# PowerModule_Testboard.net
KiCad netlist of a schematic drawn in EAGLE
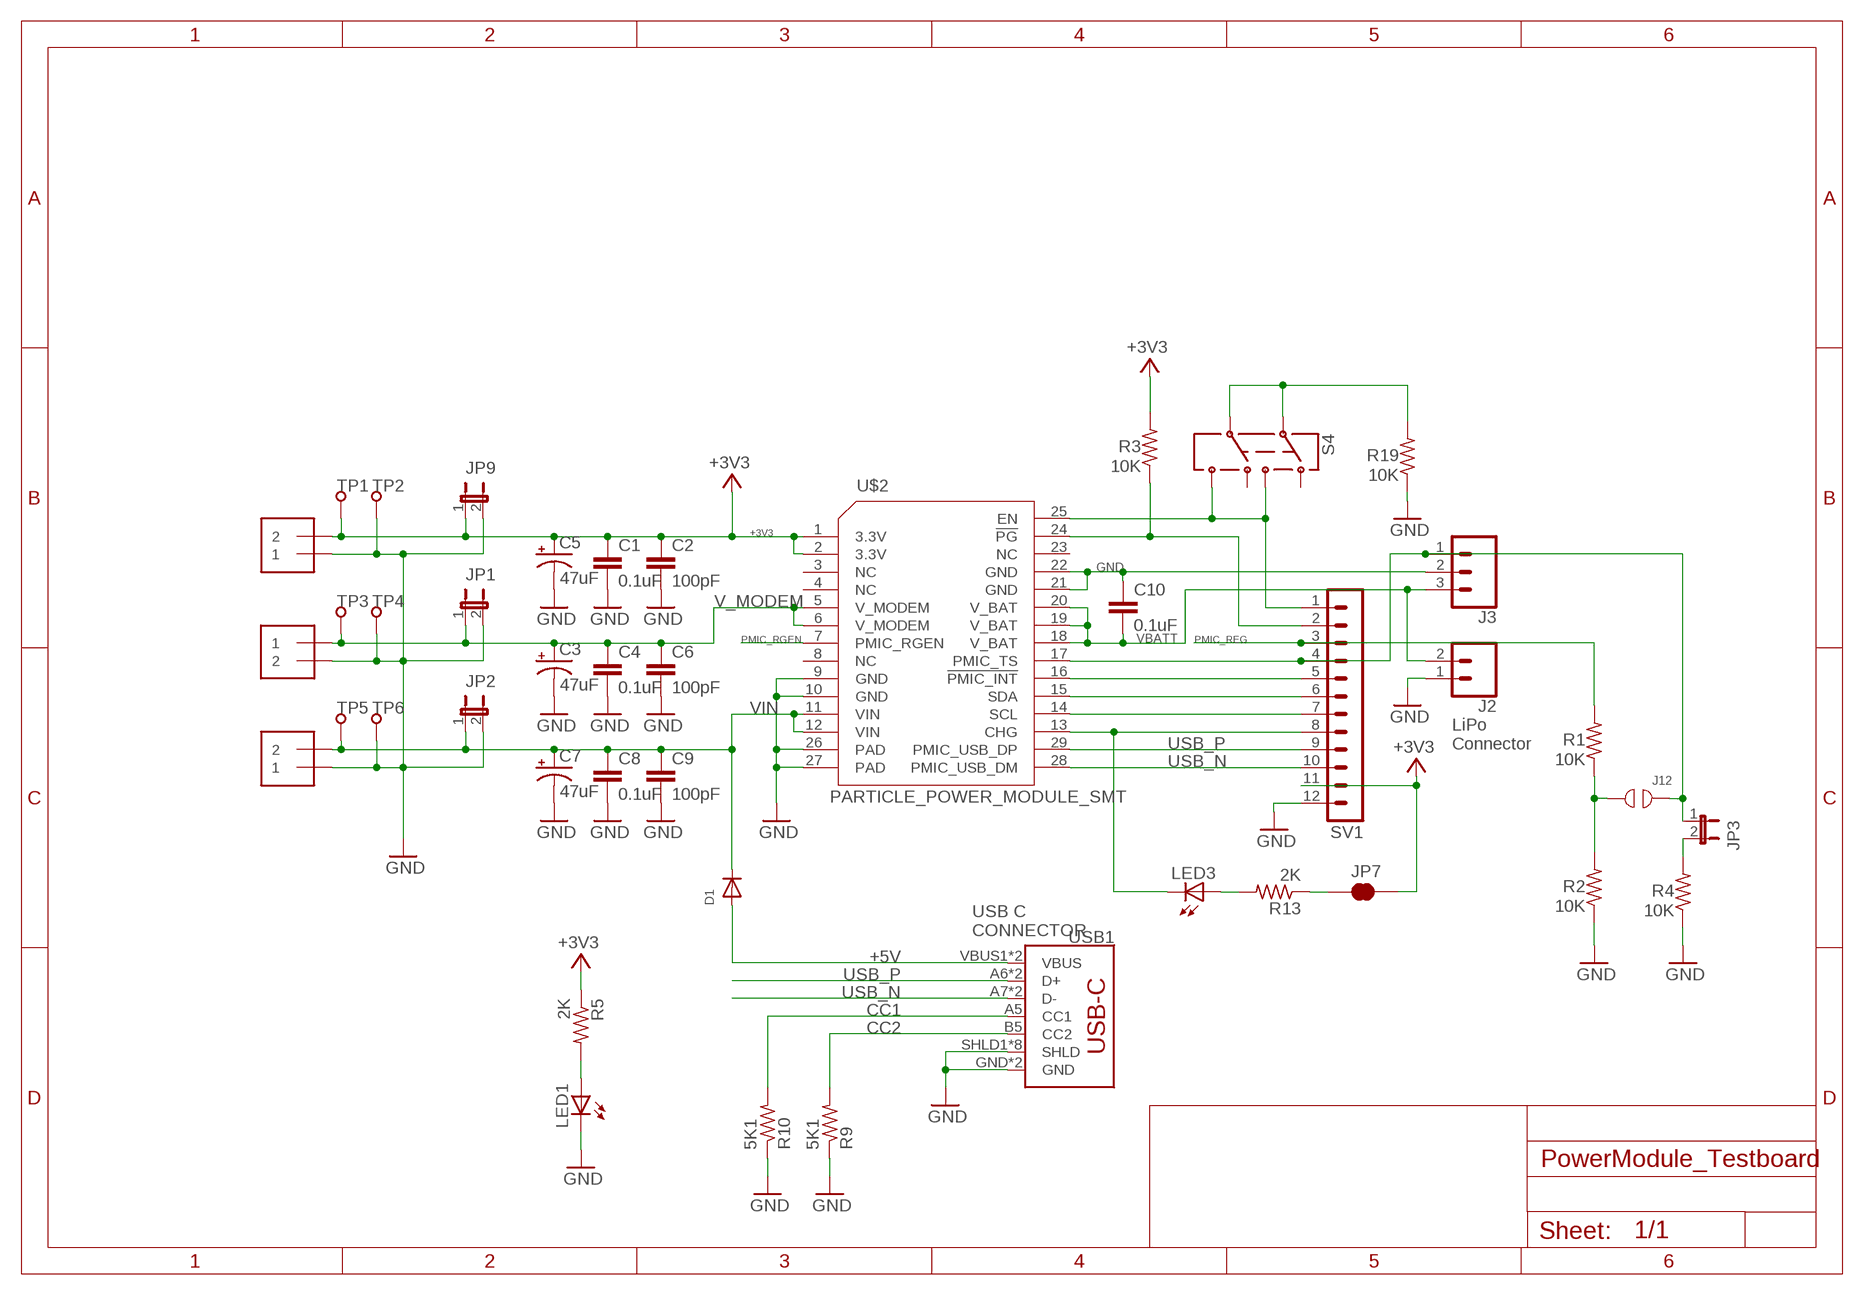
[diagram p0: schematic, sheet 1]

(export (version "E")
  (design (tool "Eeschema 10.0.6"))
  (components
    (comp (ref "C1")
      (value "0.1uF")
      (footprint "eagle-import:0603")
      (libsource (lib "eagle-import") (part "0.1UF-0603-25V-5%"))
    )
    (comp (ref "C2")
      (value "100pF")
      (footprint "eagle-import:0603")
      (libsource (lib "eagle-import") (part "0.1UF-0603-25V-5%"))
    )
    (comp (ref "C3")
      (value "47uF")
      (footprint "eagle-import:NIC_10X10.5_CAP")
      (libsource (lib "eagle-import") (part "100UF-POLAR-10X10.5-63V-20%"))
    )
    (comp (ref "C4")
      (value "0.1uF")
      (footprint "eagle-import:0603")
      (libsource (lib "eagle-import") (part "0.1UF-0603-25V-5%"))
    )
    (comp (ref "C5")
      (value "47uF")
      (footprint "eagle-import:NIC_10X10.5_CAP")
      (libsource (lib "eagle-import") (part "100UF-POLAR-10X10.5-63V-20%"))
    )
    (comp (ref "C6")
      (value "100pF")
      (footprint "eagle-import:0603")
      (libsource (lib "eagle-import") (part "0.1UF-0603-25V-5%"))
    )
    (comp (ref "C7")
      (value "47uF")
      (footprint "eagle-import:NIC_10X10.5_CAP")
      (libsource (lib "eagle-import") (part "100UF-POLAR-10X10.5-63V-20%"))
    )
    (comp (ref "C8")
      (value "0.1uF")
      (footprint "eagle-import:0603")
      (libsource (lib "eagle-import") (part "0.1UF-0603-25V-5%"))
    )
    (comp (ref "C9")
      (value "100pF")
      (footprint "eagle-import:0603")
      (libsource (lib "eagle-import") (part "0.1UF-0603-25V-5%"))
    )
    (comp (ref "C10")
      (value "0.1uF")
      (footprint "eagle-import:0603")
      (libsource (lib "eagle-import") (part "0.1UF-0603-25V-5%"))
    )
    (comp (ref "D1")
      (value "DIODE_SOD-123FL")
      (footprint "eagle-import:SOD-123FL")
      (libsource (lib "eagle-import") (part "DIODE_SOD-123FL"))
    )
    (comp (ref "J1")
      (value "1X2-3.5MM")
      (footprint "eagle-import:1X2-3.5MM")
      (libsource (lib "eagle-import") (part "1X2-3.5MM"))
    )
    (comp (ref "J2")
      (value "CONN_02-JST-2MM-SMT")
      (footprint "eagle-import:JST-2-SMD@2")
      (libsource (lib "eagle-import") (part "CONN_02-JST-2MM-SMT"))
    )
    (comp (ref "J3")
      (value "CONN_03JST-SMD-VERT")
      (footprint "eagle-import:JST-3-SMD-VERT")
      (libsource (lib "eagle-import") (part "CONN_03JST-SMD-VERT"))
    )
    (comp (ref "J4")
      (value "1X2-3.5MM")
      (footprint "eagle-import:1X2-3.5MM")
      (libsource (lib "eagle-import") (part "1X2-3.5MM"))
    )
    (comp (ref "J5")
      (value "1X2-3.5MM")
      (footprint "eagle-import:1X2-3.5MM")
      (libsource (lib "eagle-import") (part "1X2-3.5MM"))
    )
    (comp (ref "J12")
      (value "TP_OPEN")
      (footprint "eagle-import:TP_OPEN")
      (libsource (lib "eagle-import") (part "TP_OPEN"))
    )
    (comp (ref "JP1")
      (value "JUMPER2")
      (footprint "eagle-import:JUMPER2")
      (libsource (lib "eagle-import") (part "JUMPER2"))
    )
    (comp (ref "JP2")
      (value "JUMPER2")
      (footprint "eagle-import:JUMPER2")
      (libsource (lib "eagle-import") (part "JUMPER2"))
    )
    (comp (ref "JP3")
      (value "JUMPER2")
      (footprint "eagle-import:JUMPER2")
      (libsource (lib "eagle-import") (part "JUMPER2"))
    )
    (comp (ref "JP7")
      (value "JUMPER-SMT_2_NC_TRACE_NO-SILK")
      (footprint "eagle-import:SMT-JUMPER_2_NC_TRACE_NO-SILK")
      (libsource (lib "eagle-import") (part "JUMPER-SMT_2_NC_TRACE_NO-SILK"))
    )
    (comp (ref "JP9")
      (value "JUMPER2")
      (footprint "eagle-import:JUMPER2")
      (libsource (lib "eagle-import") (part "JUMPER2"))
    )
    (comp (ref "LED1")
      (value "LEDCHIP-LED0603")
      (footprint "eagle-import:CHIP-LED0603")
      (libsource (lib "eagle-import") (part "LEDCHIP-LED0603"))
    )
    (comp (ref "LED3")
      (value "LEDCHIP-LED0603")
      (footprint "eagle-import:CHIP-LED0603")
      (libsource (lib "eagle-import") (part "LEDCHIP-LED0603"))
    )
    (comp (ref "R1")
      (value "10K")
      (footprint "eagle-import:R0603_P")
      (libsource (lib "eagle-import") (part "RES_0603100K_"))
    )
    (comp (ref "R2")
      (value "10K")
      (footprint "eagle-import:R0603_P")
      (libsource (lib "eagle-import") (part "RES_0603100K_"))
    )
    (comp (ref "R3")
      (value "10K")
      (footprint "eagle-import:R0603_P")
      (libsource (lib "eagle-import") (part "RES_0603100K_"))
    )
    (comp (ref "R4")
      (value "10K")
      (footprint "eagle-import:R0603_P")
      (libsource (lib "eagle-import") (part "RES_0603100K_"))
    )
    (comp (ref "R5")
      (value "2K")
      (footprint "eagle-import:R0603_P")
      (libsource (lib "eagle-import") (part "RES_06032K2_"))
    )
    (comp (ref "R9")
      (value "5K1")
      (footprint "eagle-import:R0603_P")
      (libsource (lib "eagle-import") (part "RES_0603"))
    )
    (comp (ref "R10")
      (value "5K1")
      (footprint "eagle-import:R0603_P")
      (libsource (lib "eagle-import") (part "RES_0603"))
    )
    (comp (ref "R13")
      (value "2K")
      (footprint "eagle-import:R0603_P")
      (libsource (lib "eagle-import") (part "RES_06032K2_"))
    )
    (comp (ref "R19")
      (value "10K")
      (footprint "eagle-import:R0603_P")
      (libsource (lib "eagle-import") (part "RES_0603100K_"))
    )
    (comp (ref "S4")
      (value "SWITCH-DPDT")
      (footprint "eagle-import:SWITCH-2.5X3.2-6")
      (libsource (lib "eagle-import") (part "SWITCH-DPDT"))
    )
    (comp (ref "SV1")
      (value "MA12-1")
      (footprint "eagle-import:MA12-1")
      (libsource (lib "eagle-import") (part "MA12-1"))
    )
    (comp (ref "TP1")
      (value "TP-S2751-46R")
      (footprint "eagle-import:S2751-46R")
      (libsource (lib "eagle-import") (part "TP-S2751-46R"))
    )
    (comp (ref "TP2")
      (value "TP-S2751-46R")
      (footprint "eagle-import:S2751-46R")
      (libsource (lib "eagle-import") (part "TP-S2751-46R"))
    )
    (comp (ref "TP3")
      (value "TP-S2751-46R")
      (footprint "eagle-import:S2751-46R")
      (libsource (lib "eagle-import") (part "TP-S2751-46R"))
    )
    (comp (ref "TP4")
      (value "TP-S2751-46R")
      (footprint "eagle-import:S2751-46R")
      (libsource (lib "eagle-import") (part "TP-S2751-46R"))
    )
    (comp (ref "TP5")
      (value "TP-S2751-46R")
      (footprint "eagle-import:S2751-46R")
      (libsource (lib "eagle-import") (part "TP-S2751-46R"))
    )
    (comp (ref "TP6")
      (value "TP-S2751-46R")
      (footprint "eagle-import:S2751-46R")
      (libsource (lib "eagle-import") (part "TP-S2751-46R"))
    )
    (comp (ref "U$2")
      (value "PARTICLE_POWER_MODULE_SMT")
      (footprint "eagle-import:PARTICLE_POWER_MODULE_SMT")
      (libsource (lib "eagle-import") (part "PARTICLE_POWER_MODULE_SMT"))
    )
    (comp (ref "USB1")
      (value "USB_C16PIN")
      (footprint "eagle-import:USB-C-16P")
      (libsource (lib "eagle-import") (part "USB_C16PIN"))
    )
  )
  (nets
    (net (code "1") (name "+3V3") (class "Default")
      (node (ref "C1") (pin "1") (pinfunction "1_1") (pintype "passive"))
      (node (ref "C2") (pin "1") (pinfunction "1_1") (pintype "passive"))
      (node (ref "C5") (pin "+") (pinfunction "+_+") (pintype "passive"))
      (node (ref "J4") (pin "2") (pinfunction "2_2") (pintype "passive"))
      (node (ref "JP7") (pin "1") (pinfunction "1_1") (pintype "passive"))
      (node (ref "JP9") (pin "1") (pinfunction "1_1") (pintype "passive"))
      (node (ref "R3") (pin "2") (pinfunction "2_2") (pintype "passive"))
      (node (ref "R5") (pin "1") (pinfunction "1_1") (pintype "passive"))
      (node (ref "SV1") (pin "11") (pinfunction "11_11") (pintype "passive"))
      (node (ref "TP1") (pin "1") (pinfunction "TP_1") (pintype "bidirectional"))
      (node (ref "U$2") (pin "1") (pinfunction "3.3V_1") (pintype "bidirectional"))
      (node (ref "U$2") (pin "2") (pinfunction "3.3V_2") (pintype "bidirectional"))
    )
    (net (code "2") (name "/+5V") (class "Default")
      (node (ref "D1") (pin "A") (pinfunction "A_A") (pintype "passive"))
      (node (ref "USB1") (pin "VBUS1") (pinfunction "VBUS_VBUS1") (pintype "bidirectional"))
      (node (ref "USB1") (pin "VBUS2") (pinfunction "VBUS_VBUS2") (pintype "bidirectional"))
    )
    (net (code "3") (name "/CC1") (class "Default")
      (node (ref "R10") (pin "2") (pinfunction "2_2") (pintype "passive"))
      (node (ref "USB1") (pin "A5") (pinfunction "CC1_A5") (pintype "bidirectional"))
    )
    (net (code "4") (name "/CC2") (class "Default")
      (node (ref "R9") (pin "2") (pinfunction "2_2") (pintype "passive"))
      (node (ref "USB1") (pin "B5") (pinfunction "CC2_B5") (pintype "bidirectional"))
    )
    (net (code "5") (name "/PMIC_REG") (class "Default")
      (node (ref "R1") (pin "2") (pinfunction "2_2") (pintype "passive"))
      (node (ref "SV1") (pin "3") (pinfunction "3_3") (pintype "passive"))
    )
    (net (code "6") (name "/PMIC_RGEN") (class "Default")
      (node (ref "U$2") (pin "7") (pinfunction "PMIC_RGEN_7") (pintype "bidirectional"))
    )
    (net (code "7") (name "/USB_N") (class "Default")
      (node (ref "SV1") (pin "10") (pinfunction "10_10") (pintype "passive"))
      (node (ref "U$2") (pin "28") (pinfunction "PMIC_USB_DM_28") (pintype "bidirectional"))
      (node (ref "USB1") (pin "A7") (pinfunction "D-_A7") (pintype "bidirectional"))
      (node (ref "USB1") (pin "B7") (pinfunction "D-_B7") (pintype "bidirectional"))
    )
    (net (code "8") (name "/USB_P") (class "Default")
      (node (ref "SV1") (pin "9") (pinfunction "9_9") (pintype "passive"))
      (node (ref "U$2") (pin "29") (pinfunction "PMIC_USB_DP_29") (pintype "bidirectional"))
      (node (ref "USB1") (pin "A6") (pinfunction "D+_A6") (pintype "bidirectional"))
      (node (ref "USB1") (pin "B6") (pinfunction "D+_B6") (pintype "bidirectional"))
    )
    (net (code "9") (name "/VBATT") (class "Default")
      (node (ref "C10") (pin "2") (pinfunction "2_2") (pintype "passive"))
      (node (ref "J2") (pin "2") (pinfunction "1_2") (pintype "passive"))
      (node (ref "J3") (pin "3") (pinfunction "3_3") (pintype "passive"))
      (node (ref "U$2") (pin "18") (pinfunction "V_BAT_18") (pintype "bidirectional"))
      (node (ref "U$2") (pin "19") (pinfunction "V_BAT_19") (pintype "bidirectional"))
      (node (ref "U$2") (pin "20") (pinfunction "V_BAT_20") (pintype "bidirectional"))
    )
    (net (code "10") (name "/VIN") (class "Default")
      (node (ref "C7") (pin "+") (pinfunction "+_+") (pintype "passive"))
      (node (ref "C8") (pin "1") (pinfunction "1_1") (pintype "passive"))
      (node (ref "C9") (pin "1") (pinfunction "1_1") (pintype "passive"))
      (node (ref "D1") (pin "C") (pinfunction "C_C") (pintype "passive"))
      (node (ref "J5") (pin "2") (pinfunction "2_2") (pintype "passive"))
      (node (ref "JP2") (pin "1") (pinfunction "1_1") (pintype "passive"))
      (node (ref "TP5") (pin "1") (pinfunction "TP_1") (pintype "bidirectional"))
      (node (ref "U$2") (pin "11") (pinfunction "VIN_11") (pintype "bidirectional"))
      (node (ref "U$2") (pin "12") (pinfunction "VIN_12") (pintype "bidirectional"))
    )
    (net (code "11") (name "/V_MODEM") (class "Default")
      (node (ref "C3") (pin "+") (pinfunction "+_+") (pintype "passive"))
      (node (ref "C4") (pin "1") (pinfunction "1_1") (pintype "passive"))
      (node (ref "C6") (pin "1") (pinfunction "1_1") (pintype "passive"))
      (node (ref "J1") (pin "1") (pinfunction "1_1") (pintype "passive"))
      (node (ref "JP1") (pin "1") (pinfunction "1_1") (pintype "passive"))
      (node (ref "TP3") (pin "1") (pinfunction "TP_1") (pintype "bidirectional"))
      (node (ref "U$2") (pin "5") (pinfunction "V_MODEM_5") (pintype "bidirectional"))
      (node (ref "U$2") (pin "6") (pinfunction "V_MODEM_6") (pintype "bidirectional"))
    )
    (net (code "12") (name "GND") (class "Default")
      (node (ref "C1") (pin "2") (pinfunction "2_2") (pintype "passive"))
      (node (ref "C10") (pin "1") (pinfunction "1_1") (pintype "passive"))
      (node (ref "C2") (pin "2") (pinfunction "2_2") (pintype "passive"))
      (node (ref "C3") (pin "-") (pinfunction "-_-") (pintype "passive"))
      (node (ref "C4") (pin "2") (pinfunction "2_2") (pintype "passive"))
      (node (ref "C5") (pin "-") (pinfunction "-_-") (pintype "passive"))
      (node (ref "C6") (pin "2") (pinfunction "2_2") (pintype "passive"))
      (node (ref "C7") (pin "-") (pinfunction "-_-") (pintype "passive"))
      (node (ref "C8") (pin "2") (pinfunction "2_2") (pintype "passive"))
      (node (ref "C9") (pin "2") (pinfunction "2_2") (pintype "passive"))
      (node (ref "J1") (pin "2") (pinfunction "2_2") (pintype "passive"))
      (node (ref "J2") (pin "1") (pinfunction "2_1") (pintype "passive"))
      (node (ref "J3") (pin "2") (pinfunction "2_2") (pintype "passive"))
      (node (ref "J4") (pin "1") (pinfunction "1_1") (pintype "passive"))
      (node (ref "J5") (pin "1") (pinfunction "1_1") (pintype "passive"))
      (node (ref "JP1") (pin "2") (pinfunction "2_2") (pintype "passive"))
      (node (ref "JP2") (pin "2") (pinfunction "2_2") (pintype "passive"))
      (node (ref "JP9") (pin "2") (pinfunction "2_2") (pintype "passive"))
      (node (ref "LED1") (pin "C") (pinfunction "C_C") (pintype "passive"))
      (node (ref "R10") (pin "1") (pinfunction "1_1") (pintype "passive"))
      (node (ref "R19") (pin "1") (pinfunction "1_1") (pintype "passive"))
      (node (ref "R2") (pin "1") (pinfunction "1_1") (pintype "passive"))
      (node (ref "R4") (pin "1") (pinfunction "1_1") (pintype "passive"))
      (node (ref "R9") (pin "1") (pinfunction "1_1") (pintype "passive"))
      (node (ref "SV1") (pin "12") (pinfunction "12_12") (pintype "passive"))
      (node (ref "TP2") (pin "1") (pinfunction "TP_1") (pintype "bidirectional"))
      (node (ref "TP4") (pin "1") (pinfunction "TP_1") (pintype "bidirectional"))
      (node (ref "TP6") (pin "1") (pinfunction "TP_1") (pintype "bidirectional"))
      (node (ref "U$2") (pin "10") (pinfunction "GND_10") (pintype "bidirectional"))
      (node (ref "U$2") (pin "21") (pinfunction "GND_21") (pintype "bidirectional"))
      (node (ref "U$2") (pin "22") (pinfunction "GND_22") (pintype "bidirectional"))
      (node (ref "U$2") (pin "26") (pinfunction "PAD_26") (pintype "bidirectional"))
      (node (ref "U$2") (pin "27") (pinfunction "PAD_27") (pintype "bidirectional"))
      (node (ref "U$2") (pin "9") (pinfunction "GND_9") (pintype "bidirectional"))
      (node (ref "USB1") (pin "GND") (pinfunction "GND_GND") (pintype "bidirectional"))
      (node (ref "USB1") (pin "GND2") (pinfunction "GND_GND2") (pintype "bidirectional"))
      (node (ref "USB1") (pin "SHLD1") (pinfunction "SHLD_SHLD1") (pintype "bidirectional"))
      (node (ref "USB1") (pin "SHLD2") (pinfunction "SHLD_SHLD2") (pintype "bidirectional"))
      (node (ref "USB1") (pin "SHLD3") (pinfunction "SHLD_SHLD3") (pintype "bidirectional"))
      (node (ref "USB1") (pin "SHLD4") (pinfunction "SHLD_SHLD4") (pintype "bidirectional"))
      (node (ref "USB1") (pin "SHLD5") (pinfunction "SHLD_SHLD5") (pintype "bidirectional"))
      (node (ref "USB1") (pin "SHLD6") (pinfunction "SHLD_SHLD6") (pintype "bidirectional"))
      (node (ref "USB1") (pin "SHLD7") (pinfunction "SHLD_SHLD7") (pintype "bidirectional"))
      (node (ref "USB1") (pin "SHLD8") (pinfunction "SHLD_SHLD8") (pintype "bidirectional"))
    )
    (net (code "13") (name "Net-(J12-Pad1)") (class "Default")
      (node (ref "J12") (pin "1") (pinfunction "1_1") (pintype "bidirectional"))
      (node (ref "R1") (pin "1") (pinfunction "1_1") (pintype "passive"))
      (node (ref "R2") (pin "2") (pinfunction "2_2") (pintype "passive"))
    )
    (net (code "14") (name "Net-(JP3-Pad2)") (class "Default")
      (node (ref "JP3") (pin "2") (pinfunction "2_2") (pintype "passive"))
      (node (ref "R4") (pin "2") (pinfunction "2_2") (pintype "passive"))
    )
    (net (code "15") (name "Net-(JP7-Pad2)") (class "Default")
      (node (ref "JP7") (pin "2") (pinfunction "2_2") (pintype "passive"))
      (node (ref "R13") (pin "1") (pinfunction "1_1") (pintype "passive"))
    )
    (net (code "16") (name "Net-(LED1-PadA)") (class "Default")
      (node (ref "LED1") (pin "A") (pinfunction "A_A") (pintype "passive"))
      (node (ref "R5") (pin "2") (pinfunction "2_2") (pintype "passive"))
    )
    (net (code "17") (name "Net-(LED3-PadA)") (class "Default")
      (node (ref "LED3") (pin "A") (pinfunction "A_A") (pintype "passive"))
      (node (ref "R13") (pin "2") (pinfunction "2_2") (pintype "passive"))
    )
    (net (code "18") (name "Net-(R19-Pad2)") (class "Default")
      (node (ref "R19") (pin "2") (pinfunction "2_2") (pintype "passive"))
      (node (ref "S4") (pin "2") (pinfunction "2_2") (pintype "bidirectional"))
      (node (ref "S4") (pin "5") (pinfunction "5_5") (pintype "bidirectional"))
    )
    (net (code "19") (name "Net-(U$2-CHG)") (class "Default")
      (node (ref "LED3") (pin "C") (pinfunction "C_C") (pintype "passive"))
      (node (ref "SV1") (pin "8") (pinfunction "8_8") (pintype "passive"))
      (node (ref "U$2") (pin "13") (pinfunction "CHG_13") (pintype "bidirectional"))
    )
    (net (code "20") (name "Net-(U$2-EN)") (class "Default")
      (node (ref "S4") (pin "3") (pinfunction "3_3") (pintype "bidirectional"))
      (node (ref "S4") (pin "6") (pinfunction "6_6") (pintype "bidirectional"))
      (node (ref "SV1") (pin "1") (pinfunction "1_1") (pintype "passive"))
      (node (ref "U$2") (pin "25") (pinfunction "EN_25") (pintype "bidirectional"))
    )
    (net (code "21") (name "Net-(U$2-PMIC_TS)") (class "Default")
      (node (ref "J12") (pin "2") (pinfunction "2_2") (pintype "bidirectional"))
      (node (ref "J3") (pin "1") (pinfunction "1_1") (pintype "passive"))
      (node (ref "JP3") (pin "1") (pinfunction "1_1") (pintype "passive"))
      (node (ref "SV1") (pin "4") (pinfunction "4_4") (pintype "passive"))
      (node (ref "U$2") (pin "17") (pinfunction "PMIC_TS_17") (pintype "bidirectional"))
    )
    (net (code "22") (name "Net-(U$2-SCL)") (class "Default")
      (node (ref "SV1") (pin "7") (pinfunction "7_7") (pintype "passive"))
      (node (ref "U$2") (pin "14") (pinfunction "SCL_14") (pintype "bidirectional"))
    )
    (net (code "23") (name "Net-(U$2-SDA)") (class "Default")
      (node (ref "SV1") (pin "6") (pinfunction "6_6") (pintype "passive"))
      (node (ref "U$2") (pin "15") (pinfunction "SDA_15") (pintype "bidirectional"))
    )
    (net (code "24") (name "Net-(U$2-~{PG})") (class "Default")
      (node (ref "R3") (pin "1") (pinfunction "1_1") (pintype "passive"))
      (node (ref "SV1") (pin "2") (pinfunction "2_2") (pintype "passive"))
      (node (ref "U$2") (pin "24") (pinfunction "~{PG}_24") (pintype "bidirectional"))
    )
    (net (code "25") (name "Net-(U$2-~{PMIC_INT})") (class "Default")
      (node (ref "SV1") (pin "5") (pinfunction "5_5") (pintype "passive"))
      (node (ref "U$2") (pin "16") (pinfunction "~{PMIC_INT}_16") (pintype "bidirectional"))
    )
    (net (code "26") (name "unconnected-(S4-Pad1)") (class "Default")
      (node (ref "S4") (pin "1") (pinfunction "1_1") (pintype "bidirectional"))
    )
    (net (code "27") (name "unconnected-(S4-Pad4)") (class "Default")
      (node (ref "S4") (pin "4") (pinfunction "4_4") (pintype "bidirectional"))
    )
    (net (code "28") (name "unconnected-(U$2-NC-Pad3)") (class "Default")
      (node (ref "U$2") (pin "3") (pinfunction "NC_3") (pintype "bidirectional"))
    )
    (net (code "29") (name "unconnected-(U$2-NC-Pad4)") (class "Default")
      (node (ref "U$2") (pin "4") (pinfunction "NC_4") (pintype "bidirectional"))
    )
    (net (code "30") (name "unconnected-(U$2-NC-Pad8)") (class "Default")
      (node (ref "U$2") (pin "8") (pinfunction "NC_8") (pintype "bidirectional"))
    )
    (net (code "31") (name "unconnected-(U$2-NC-Pad23)") (class "Default")
      (node (ref "U$2") (pin "23") (pinfunction "NC_23") (pintype "bidirectional"))
    )
  )
)
